# Sheet1.net
KiCad netlist of a schematic drawn in Altium Designer
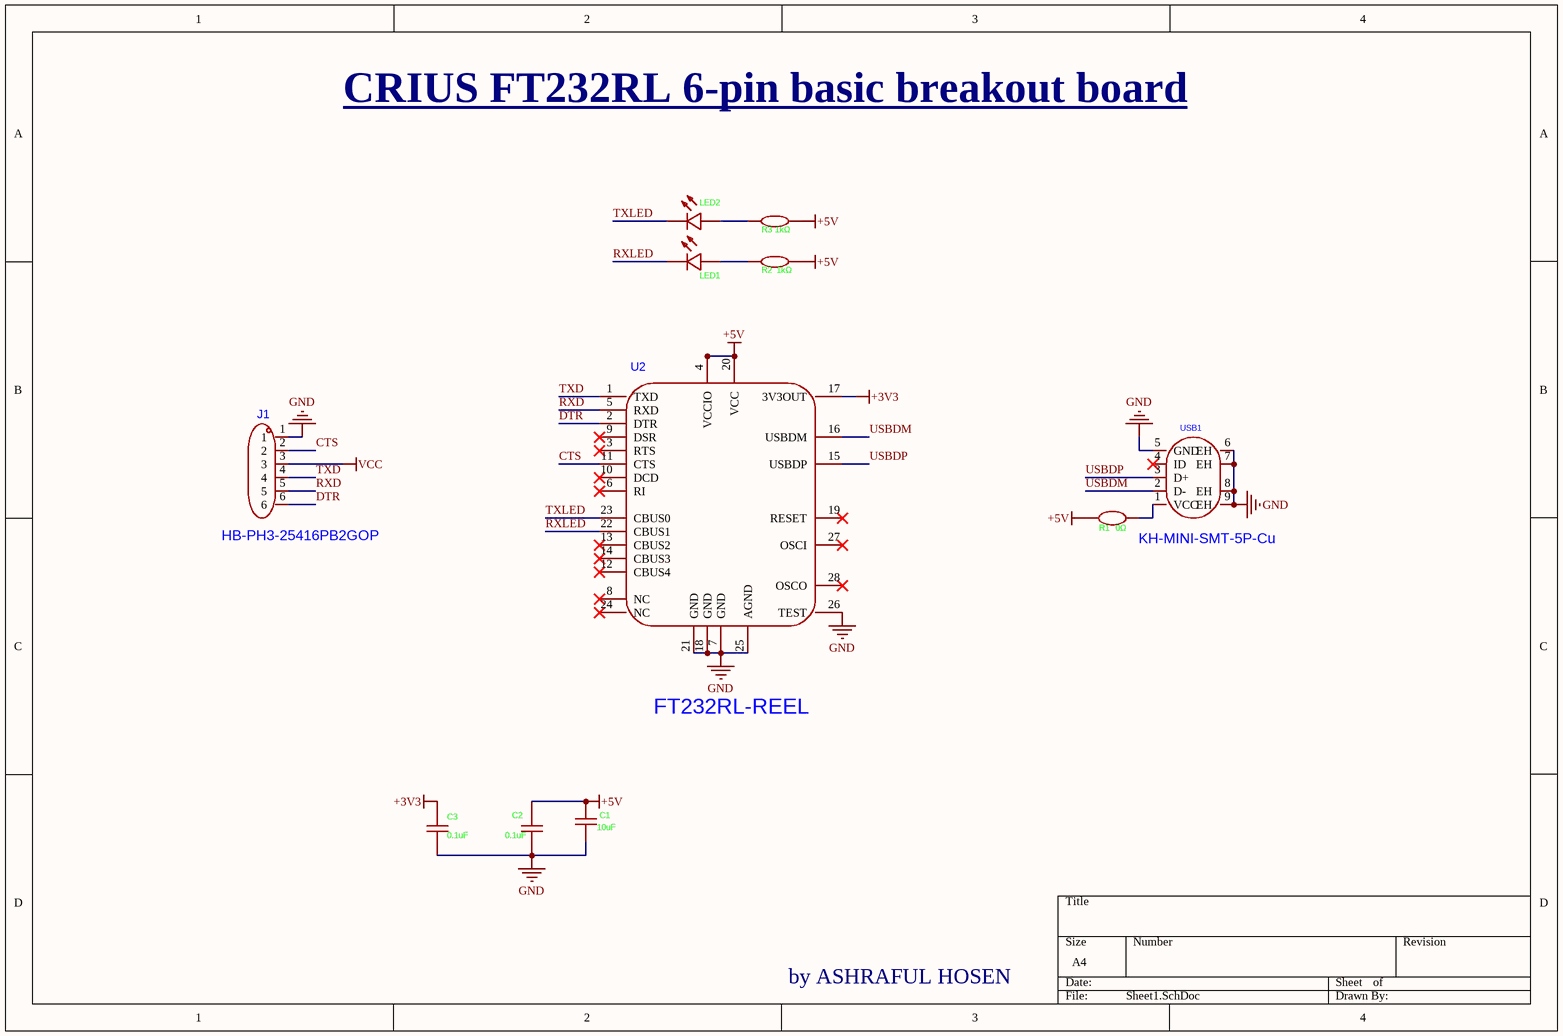
[diagram p0: Sheet1.SchDoc]

(export (version "E")
  (design (tool "Eeschema 10.0.6"))
  (components
    (comp (ref "C1")
      (value "10uF")
      (footprint "C1206")
      (description "50V 10uF X5R ±10% 1206 Multilayer Ceramic Capacitors MLCC - SMD/SMT ROHS")
      (fields
        (field (name "MANUFACTURER") "SAMSUNG(三星)")
        (field (name "MANUFACTURER PART") "CL31A106KBHNNNE")
      )
      (libsource (lib "Schlib1") (part "CL31A106KBHNNNE"))
    )
    (comp (ref "C2")
      (value "0.1uF")
      (footprint "C0603")
      (description "50V 100nF X7R ±10% 0603 Multilayer Ceramic Capacitors MLCC - SMD/SMT ROHS")
      (fields
        (field (name "MANUFACTURER") "YAGEO(国巨)")
        (field (name "MANUFACTURER PART") "CC0603KRX7R9BB104")
      )
      (libsource (lib "Schlib1") (part "CC0603KRX7R9BB104"))
    )
    (comp (ref "C3")
      (value "0.1uF")
      (footprint "C0603")
      (description "50V 100nF X7R ±10% 0603 Multilayer Ceramic Capacitors MLCC - SMD/SMT ROHS")
      (fields
        (field (name "MANUFACTURER") "YAGEO(国巨)")
        (field (name "MANUFACTURER PART") "CC0603KRX7R9BB104")
      )
      (libsource (lib "Schlib1") (part "CC0603KRX7R9BB104"))
    )
    (comp (ref "J1")
      (value "HB-PH3-25416PB2GOP")
      (footprint "HDR-TH_6P-P2.54-V-M")
      (fields (field (name "MANUFACTURER") "HANBO(汉博)"))
      (libsource (lib "Schlib1") (part "HB-PH3-25416PB2GOP"))
    )
    (comp (ref "LED1")
      (value "19-217/R6C-AL1M2VY/3T")
      (footprint "LED0603-RD")
      (description "5mA Water Clear -40℃~+85℃ 617.5nm Red 120° 60mW 1.95V 0603 LED Indication - Discrete ROHS")
      (fields (field (name "MANUFACTURER") "EVERLIGHT(亿光)"))
      (libsource (lib "Schlib1") (part "19-217/R6C-AL1M2VY/3T"))
    )
    (comp (ref "LED2")
      (value "19-217/R6C-AL1M2VY/3T")
      (footprint "LED0603-RD")
      (description "5mA Water Clear -40℃~+85℃ 617.5nm Red 120° 60mW 1.95V 0603 LED Indication - Discrete ROHS")
      (fields (field (name "MANUFACTURER") "EVERLIGHT(亿光)"))
      (libsource (lib "Schlib1") (part "19-217/R6C-AL1M2VY/3T"))
    )
    (comp (ref "R1")
      (value "0Ω")
      (footprint "R0805")
      (description "125mW Thick Film Resistor 150V ±5% 0Ω 0805 Chip Resistor - Surface Mount ROHS")
      (fields (field (name "MANUFACTURER") "FOJAN(富捷)") (field (name "MANUFACTURER PART") "FRC0805P000 TS"))
      (libsource (lib "Schlib1") (part "FRC0805P000 TS"))
    )
    (comp (ref "R2")
      (value "1kΩ")
      (footprint "R0603")
      (description "100mW Thick Film Resistor 75V ±100ppm/℃ ±1% 1kΩ 0603 Chip Resistor - Surface Mount ROHS")
      (fields (field (name "MANUFACTURER") "YAGEO(国巨)") (field (name "MANUFACTURER PART") "RC0603FR-071KL"))
      (libsource (lib "Schlib1") (part "RC0603FR-071KL"))
    )
    (comp (ref "R3")
      (value "1kΩ")
      (footprint "R0603")
      (description "100mW Thick Film Resistor 75V ±100ppm/℃ ±1% 1kΩ 0603 Chip Resistor - Surface Mount ROHS")
      (fields (field (name "MANUFACTURER") "YAGEO(国巨)") (field (name "MANUFACTURER PART") "RC0603FR-071KL"))
      (libsource (lib "Schlib1") (part "RC0603FR-071KL"))
    )
    (comp (ref "U2")
      (value "FT232RL-REEL")
      (footprint "SSOP-28_L10.2-W5.3-P0.65-LS7.8-BL")
      (description "USB to UART SSOP-28-208mil USB Converters ROHS")
      (fields (field (name "MANUFACTURER") "FTDI(飞特帝亚)"))
      (libsource (lib "Schlib1") (part "FT232RL-REEL"))
    )
    (comp (ref "USB1")
      (value "KH-MINI-SMT-5P-Cu")
      (footprint "MINI-USB-SMD_KH-MINI-SMT-5P-CU")
      (description "1A USB 2.0 1 Surface Mount, Right Angle 5P Female Mini-B SMD USB Connectors ROHS")
      (fields (field (name "MANUFACTURER") "kinghelm(金航标)"))
      (libsource (lib "Schlib1") (part "KH-MINI-SMT-5P-Cu"))
    )
  )
  (nets
    (net (code "1") (name "+3V3") (class "Default")
      (node (ref "C3") (pin "2") (pinfunction "2_2") (pintype "passive"))
      (node (ref "U2") (pin "17") (pinfunction "3V3OUT_17") (pintype "passive"))
    )
    (net (code "2") (name "+5V") (class "Default")
      (node (ref "C1") (pin "2") (pinfunction "2_2") (pintype "passive"))
      (node (ref "C2") (pin "2") (pinfunction "2_2") (pintype "passive"))
      (node (ref "R1") (pin "1") (pinfunction "1_1") (pintype "passive"))
      (node (ref "R2") (pin "2") (pinfunction "2_2") (pintype "passive"))
      (node (ref "R3") (pin "2") (pinfunction "2_2") (pintype "passive"))
      (node (ref "U2") (pin "20") (pinfunction "VCC_20") (pintype "passive"))
      (node (ref "U2") (pin "4") (pinfunction "VCCIO_4") (pintype "passive"))
    )
    (net (code "3") (name "/CTS") (class "Default")
      (node (ref "J1") (pin "2") (pinfunction "2_2") (pintype "passive"))
      (node (ref "U2") (pin "11") (pinfunction "CTS_11") (pintype "passive"))
    )
    (net (code "4") (name "/DTR") (class "Default")
      (node (ref "J1") (pin "6") (pinfunction "6_6") (pintype "passive"))
      (node (ref "U2") (pin "2") (pinfunction "DTR_2") (pintype "passive"))
    )
    (net (code "5") (name "/RXD") (class "Default")
      (node (ref "J1") (pin "5") (pinfunction "5_5") (pintype "passive"))
      (node (ref "U2") (pin "5") (pinfunction "RXD_5") (pintype "passive"))
    )
    (net (code "6") (name "/RXLED") (class "Default")
      (node (ref "LED1") (pin "1") (pinfunction "C_1") (pintype "passive"))
      (node (ref "U2") (pin "22") (pinfunction "CBUS1_22") (pintype "passive"))
    )
    (net (code "7") (name "/TXD") (class "Default")
      (node (ref "J1") (pin "4") (pinfunction "4_4") (pintype "passive"))
      (node (ref "U2") (pin "1") (pinfunction "TXD_1") (pintype "passive"))
    )
    (net (code "8") (name "/TXLED") (class "Default")
      (node (ref "LED2") (pin "1") (pinfunction "C_1") (pintype "passive"))
      (node (ref "U2") (pin "23") (pinfunction "CBUS0_23") (pintype "passive"))
    )
    (net (code "9") (name "/USBDM") (class "Default")
      (node (ref "U2") (pin "16") (pinfunction "USBDM_16") (pintype "passive"))
      (node (ref "USB1") (pin "2") (pinfunction "D-_2") (pintype "passive"))
    )
    (net (code "10") (name "/USBDP") (class "Default")
      (node (ref "U2") (pin "15") (pinfunction "USBDP_15") (pintype "passive"))
      (node (ref "USB1") (pin "3") (pinfunction "D+_3") (pintype "passive"))
    )
    (net (code "11") (name "GND") (class "Default")
      (node (ref "C1") (pin "1") (pinfunction "1_1") (pintype "passive"))
      (node (ref "C2") (pin "1") (pinfunction "1_1") (pintype "passive"))
      (node (ref "C3") (pin "1") (pinfunction "1_1") (pintype "passive"))
      (node (ref "J1") (pin "1") (pinfunction "1_1") (pintype "passive"))
      (node (ref "U2") (pin "18") (pinfunction "GND_18") (pintype "passive"))
      (node (ref "U2") (pin "21") (pinfunction "GND_21") (pintype "passive"))
      (node (ref "U2") (pin "25") (pinfunction "AGND_25") (pintype "passive"))
      (node (ref "U2") (pin "26") (pinfunction "TEST_26") (pintype "passive"))
      (node (ref "U2") (pin "7") (pinfunction "GND_7") (pintype "passive"))
      (node (ref "USB1") (pin "5") (pinfunction "GND_5") (pintype "passive"))
      (node (ref "USB1") (pin "6") (pinfunction "EH_6") (pintype "passive"))
      (node (ref "USB1") (pin "7") (pinfunction "EH_7") (pintype "passive"))
      (node (ref "USB1") (pin "8") (pinfunction "EH_8") (pintype "passive"))
      (node (ref "USB1") (pin "9") (pinfunction "EH_9") (pintype "passive"))
    )
    (net (code "12") (name "Net-(LED1-A)") (class "Default")
      (node (ref "LED1") (pin "2") (pinfunction "A_2") (pintype "passive"))
      (node (ref "R2") (pin "1") (pinfunction "1_1") (pintype "passive"))
    )
    (net (code "13") (name "Net-(LED2-A)") (class "Default")
      (node (ref "LED2") (pin "2") (pinfunction "A_2") (pintype "passive"))
      (node (ref "R3") (pin "1") (pinfunction "1_1") (pintype "passive"))
    )
    (net (code "14") (name "Net-(USB1-VCC)") (class "Default")
      (node (ref "R1") (pin "2") (pinfunction "2_2") (pintype "passive"))
      (node (ref "USB1") (pin "1") (pinfunction "VCC_1") (pintype "passive"))
    )
    (net (code "15") (name "VCC") (class "Default")
      (node (ref "J1") (pin "3") (pinfunction "3_3") (pintype "passive"))
    )
    (net (code "16") (name "unconnected-(U2-CBUS2-Pad13)") (class "Default")
      (node (ref "U2") (pin "13") (pinfunction "CBUS2_13") (pintype "passive+no_connect"))
    )
    (net (code "17") (name "unconnected-(U2-CBUS3-Pad14)") (class "Default")
      (node (ref "U2") (pin "14") (pinfunction "CBUS3_14") (pintype "passive+no_connect"))
    )
    (net (code "18") (name "unconnected-(U2-CBUS4-Pad12)") (class "Default")
      (node (ref "U2") (pin "12") (pinfunction "CBUS4_12") (pintype "passive+no_connect"))
    )
    (net (code "19") (name "unconnected-(U2-DCD-Pad10)") (class "Default")
      (node (ref "U2") (pin "10") (pinfunction "DCD_10") (pintype "passive+no_connect"))
    )
    (net (code "20") (name "unconnected-(U2-DSR-Pad9)") (class "Default")
      (node (ref "U2") (pin "9") (pinfunction "DSR_9") (pintype "passive+no_connect"))
    )
    (net (code "21") (name "unconnected-(U2-NC-Pad8)") (class "Default")
      (node (ref "U2") (pin "8") (pinfunction "NC_8") (pintype "passive+no_connect"))
    )
    (net (code "22") (name "unconnected-(U2-NC-Pad24)") (class "Default")
      (node (ref "U2") (pin "24") (pinfunction "NC_24") (pintype "passive+no_connect"))
    )
    (net (code "23") (name "unconnected-(U2-OSCI-Pad27)") (class "Default")
      (node (ref "U2") (pin "27") (pinfunction "OSCI_27") (pintype "passive+no_connect"))
    )
    (net (code "24") (name "unconnected-(U2-OSCO-Pad28)") (class "Default")
      (node (ref "U2") (pin "28") (pinfunction "OSCO_28") (pintype "passive+no_connect"))
    )
    (net (code "25") (name "unconnected-(U2-RESET-Pad19)") (class "Default")
      (node (ref "U2") (pin "19") (pinfunction "RESET_19") (pintype "passive+no_connect"))
    )
    (net (code "26") (name "unconnected-(U2-RI-Pad6)") (class "Default")
      (node (ref "U2") (pin "6") (pinfunction "RI_6") (pintype "passive+no_connect"))
    )
    (net (code "27") (name "unconnected-(U2-RTS-Pad3)") (class "Default")
      (node (ref "U2") (pin "3") (pinfunction "RTS_3") (pintype "passive+no_connect"))
    )
    (net (code "28") (name "unconnected-(USB1-ID-Pad4)") (class "Default")
      (node (ref "USB1") (pin "4") (pinfunction "ID_4") (pintype "passive+no_connect"))
    )
  )
)
